# MEGA-JTAG.net
KiCad netlist of a schematic drawn in EAGLE
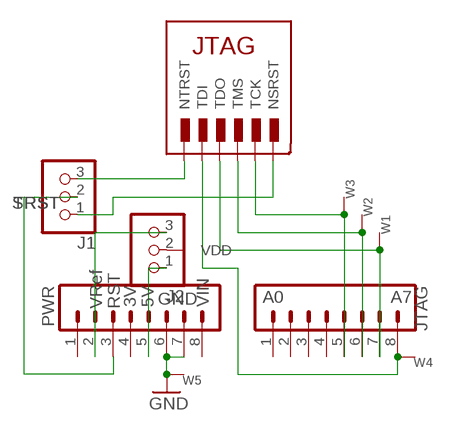
[diagram p0: schematic, sheet 1]

(export (version "E")
  (design (tool "Eeschema 10.0.6"))
  (components
    (comp (ref "J1")
      (value "JUMPER_1X3ALT")
      (footprint "eagle-import:JUMPER_SOLDER")
      (fields (field (name "J12") "SRST") (field (name "J23") "TRST"))
      (libsource (lib "eagle-import") (part "JUMPER_1X3ALT"))
    )
    (comp (ref "J2")
      (value "JUMPER_1X3ALT")
      (footprint "eagle-import:JUMPER_SOLDER")
      (libsource (lib "eagle-import") (part "JUMPER_1X3ALT"))
    )
    (comp (ref "JP1")
      (value "JTAG")
      (footprint "eagle-import:1X08_LOCK_LONGPADS")
      (libsource (lib "eagle-import") (part "M08LOCK_LONGPADS"))
    )
    (comp (ref "JP2")
      (value "PWR")
      (footprint "eagle-import:1X08_LOCK_LONGPADS")
      (libsource (lib "eagle-import") (part "M08LOCK_LONGPADS"))
    )
    (comp (ref "U$1")
      (value "JTAG6/10")
      (footprint "eagle-import:JTAG10")
      (libsource (lib "eagle-import") (part "JTAG6/10"))
    )
    (comp (ref "W1")
      (value "WIRE-VIA8")
      (footprint "eagle-import:VIA8")
      (libsource (lib "eagle-import") (part "WIRE-VIA8"))
    )
    (comp (ref "W2")
      (value "WIRE-VIA8")
      (footprint "eagle-import:VIA8")
      (libsource (lib "eagle-import") (part "WIRE-VIA8"))
    )
    (comp (ref "W3")
      (value "WIRE-VIA8")
      (footprint "eagle-import:VIA8")
      (libsource (lib "eagle-import") (part "WIRE-VIA8"))
    )
    (comp (ref "W4")
      (value "WIRE-VIA8")
      (footprint "eagle-import:VIA8")
      (libsource (lib "eagle-import") (part "WIRE-VIA8"))
    )
    (comp (ref "W5")
      (value "WIRE-VIA8")
      (footprint "eagle-import:VIA8")
      (libsource (lib "eagle-import") (part "WIRE-VIA8"))
    )
  )
  (nets
    (net (code "1") (name "GND") (class "Default")
      (node (ref "JP2") (pin "6") (pinfunction "6_6") (pintype "passive"))
      (node (ref "JP2") (pin "7") (pinfunction "7_7") (pintype "passive"))
      (node (ref "W5") (pin "P$1") (pinfunction "P$1_P$1") (pintype "bidirectional"))
    )
    (net (code "2") (name "Net-(J1-Pad2)") (class "Default")
      (node (ref "J1") (pin "2") (pinfunction "2_2") (pintype "passive"))
      (node (ref "JP2") (pin "3") (pinfunction "3_3") (pintype "passive"))
    )
    (net (code "3") (name "Net-(J2-Pad1)") (class "Default")
      (node (ref "J2") (pin "1") (pinfunction "1_1") (pintype "passive"))
      (node (ref "JP2") (pin "5") (pinfunction "5_5") (pintype "passive"))
    )
    (net (code "4") (name "Net-(J2-Pad3)") (class "Default")
      (node (ref "J2") (pin "3") (pinfunction "3_3") (pintype "passive"))
      (node (ref "JP2") (pin "2") (pinfunction "2_2") (pintype "passive"))
    )
    (net (code "5") (name "Net-(U$1A-NSRST)") (class "Default")
      (node (ref "J1") (pin "1") (pinfunction "1_1") (pintype "passive"))
      (node (ref "U$1") (pin "6.NSRST") (pinfunction "NSRST_6.NSRST") (pintype "bidirectional"))
    )
    (net (code "6") (name "Net-(U$1A-NTRST)") (class "Default")
      (node (ref "J1") (pin "3") (pinfunction "3_3") (pintype "passive"))
      (node (ref "U$1") (pin "8.NTRST") (pinfunction "NTRST_8.NTRST") (pintype "bidirectional"))
    )
    (net (code "7") (name "Net-(U$1A-TCK)") (class "Default")
      (node (ref "JP1") (pin "5") (pinfunction "5_5") (pintype "passive"))
      (node (ref "U$1") (pin "1.TCK") (pinfunction "TCK_1.TCK") (pintype "bidirectional"))
      (node (ref "W3") (pin "P$1") (pinfunction "P$1_P$1") (pintype "bidirectional"))
    )
    (net (code "8") (name "Net-(U$1A-TDI)") (class "Default")
      (node (ref "JP1") (pin "8") (pinfunction "8_8") (pintype "passive"))
      (node (ref "U$1") (pin "9.TDI") (pinfunction "TDI_9.TDI") (pintype "bidirectional"))
      (node (ref "W4") (pin "P$1") (pinfunction "P$1_P$1") (pintype "bidirectional"))
    )
    (net (code "9") (name "Net-(U$1A-TDO)") (class "Default")
      (node (ref "JP1") (pin "7") (pinfunction "7_7") (pintype "passive"))
      (node (ref "U$1") (pin "3.TDO") (pinfunction "TDO_3.TDO") (pintype "bidirectional"))
      (node (ref "W1") (pin "P$1") (pinfunction "P$1_P$1") (pintype "bidirectional"))
    )
    (net (code "10") (name "Net-(U$1A-TMS)") (class "Default")
      (node (ref "JP1") (pin "6") (pinfunction "6_6") (pintype "passive"))
      (node (ref "U$1") (pin "5.TMS") (pinfunction "TMS_5.TMS") (pintype "bidirectional"))
      (node (ref "W2") (pin "P$1") (pinfunction "P$1_P$1") (pintype "bidirectional"))
    )
    (net (code "11") (name "Net-(U$1D-VDD)") (class "Default")
      (node (ref "J2") (pin "2") (pinfunction "2_2") (pintype "passive"))
      (node (ref "U$1") (pin "4.VTREF") (pinfunction "VDD_4.VTREF") (pintype "power_in"))
    )
    (net (code "12") (name "unconnected-(JP1-Pad1)") (class "Default")
      (node (ref "JP1") (pin "1") (pinfunction "1_1") (pintype "passive"))
    )
    (net (code "13") (name "unconnected-(JP1-Pad2)") (class "Default")
      (node (ref "JP1") (pin "2") (pinfunction "2_2") (pintype "passive"))
    )
    (net (code "14") (name "unconnected-(JP1-Pad3)") (class "Default")
      (node (ref "JP1") (pin "3") (pinfunction "3_3") (pintype "passive"))
    )
    (net (code "15") (name "unconnected-(JP1-Pad4)") (class "Default")
      (node (ref "JP1") (pin "4") (pinfunction "4_4") (pintype "passive"))
    )
    (net (code "16") (name "unconnected-(JP2-Pad1)") (class "Default")
      (node (ref "JP2") (pin "1") (pinfunction "1_1") (pintype "passive"))
    )
    (net (code "17") (name "unconnected-(JP2-Pad4)") (class "Default")
      (node (ref "JP2") (pin "4") (pinfunction "4_4") (pintype "passive"))
    )
    (net (code "18") (name "unconnected-(JP2-Pad8)") (class "Default")
      (node (ref "JP2") (pin "8") (pinfunction "8_8") (pintype "passive"))
    )
  )
)
